# 2MB-Gary-Sel-v3.net
KiCad netlist of a schematic drawn in EAGLE
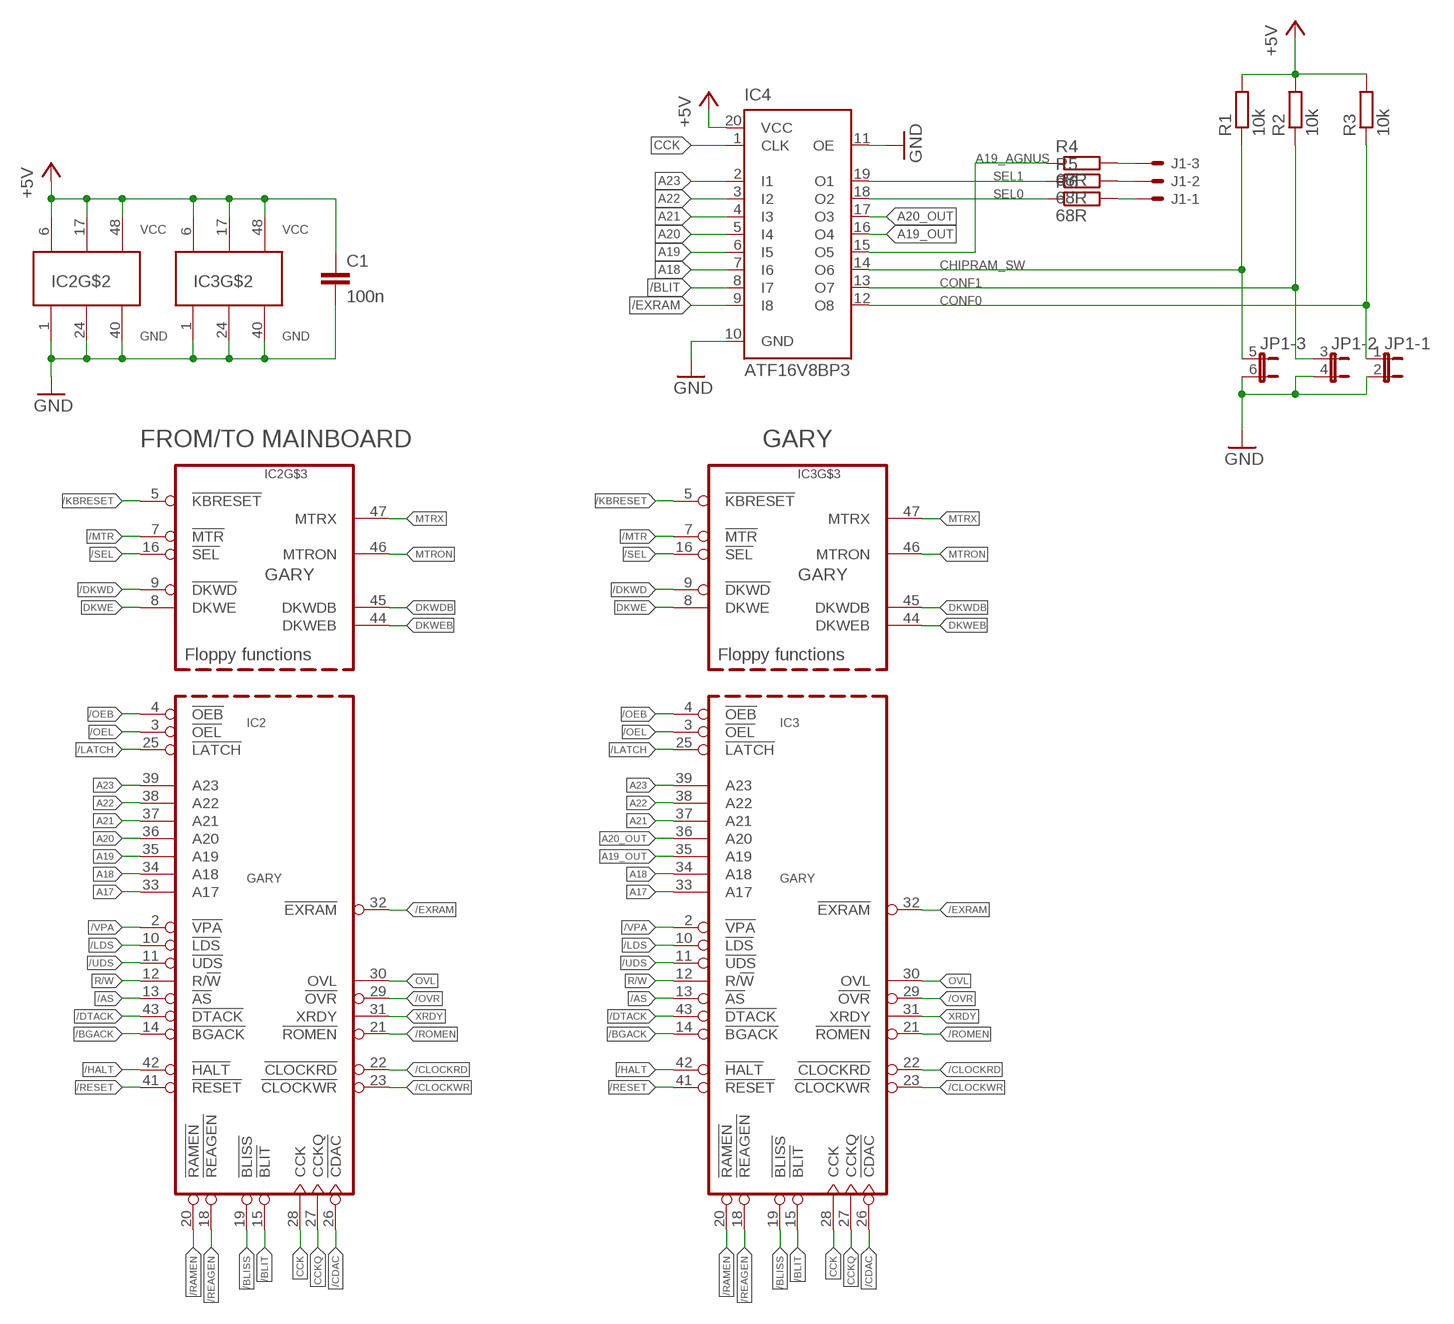
[diagram p0: schematic, sheet 1]

(export (version "E")
  (design (tool "Eeschema 10.0.6"))
  (components
    (comp (ref "C1")
      (value "100n")
      (footprint "eagle-import:C0805")
      (libsource (lib "eagle-import") (part "C-EUC0805"))
    )
    (comp (ref "IC2")
      (value "GARY_SOCKET")
      (footprint "eagle-import:DIP48-6NOPLACE")
      (libsource (lib "eagle-import") (part "GARYDIP48-6NOPLACE"))
    )
    (comp (ref "IC3")
      (value "GARY")
      (footprint "eagle-import:DIP48-6")
      (libsource (lib "eagle-import") (part "GARY_DIP"))
    )
    (comp (ref "IC4")
      (value "ATF16V8BP3")
      (footprint "eagle-import:DIL20")
      (fields (field (name "MPN") "ATF16V8CZ-15PU"))
      (libsource (lib "eagle-import") (part "ATF16V8BP3"))
    )
    (comp (ref "J1")
      (value "22-05-7038-03")
      (footprint "eagle-import:7395-03")
      (libsource (lib "eagle-import") (part "22-?-0305-7038"))
    )
    (comp (ref "JP1")
      (value "JP3QE")
      (footprint "eagle-import:JP3Q")
      (libsource (lib "eagle-import") (part "JP3QE"))
    )
    (comp (ref "R1")
      (value "10k")
      (footprint "eagle-import:R0805")
      (libsource (lib "eagle-import") (part "R-EU_R0805"))
    )
    (comp (ref "R2")
      (value "10k")
      (footprint "eagle-import:R0805")
      (libsource (lib "eagle-import") (part "R-EU_R0805"))
    )
    (comp (ref "R3")
      (value "10k")
      (footprint "eagle-import:R0805")
      (libsource (lib "eagle-import") (part "R-EU_R0805"))
    )
    (comp (ref "R4")
      (value "68R")
      (footprint "eagle-import:R0805")
      (libsource (lib "eagle-import") (part "R-EU_R0805"))
    )
    (comp (ref "R5")
      (value "68R")
      (footprint "eagle-import:R0805")
      (libsource (lib "eagle-import") (part "R-EU_R0805"))
    )
    (comp (ref "R6")
      (value "68R")
      (footprint "eagle-import:R0805")
      (libsource (lib "eagle-import") (part "R-EU_R0805"))
    )
  )
  (nets
    (net (code "1") (name "+5V") (class "Default")
      (node (ref "C1") (pin "1") (pinfunction "1_1") (pintype "passive"))
      (node (ref "IC2") (pin "17") (pinfunction "VCC_17") (pintype "power_in"))
      (node (ref "IC2") (pin "48") (pinfunction "VCC_48") (pintype "power_in"))
      (node (ref "IC2") (pin "6") (pinfunction "VCC_6") (pintype "power_in"))
      (node (ref "IC3") (pin "17") (pinfunction "VCC_17") (pintype "power_in"))
      (node (ref "IC3") (pin "48") (pinfunction "VCC_48") (pintype "power_in"))
      (node (ref "IC3") (pin "6") (pinfunction "VCC_6") (pintype "power_in"))
      (node (ref "IC4") (pin "20") (pinfunction "VCC_20") (pintype "power_in"))
      (node (ref "R1") (pin "2") (pinfunction "2_2") (pintype "passive"))
      (node (ref "R2") (pin "2") (pinfunction "2_2") (pintype "passive"))
      (node (ref "R3") (pin "2") (pinfunction "2_2") (pintype "passive"))
    )
    (net (code "2") (name "/A19_AGNUS") (class "Default")
      (node (ref "IC4") (pin "15") (pinfunction "O5_15") (pintype "output"))
      (node (ref "R4") (pin "1") (pinfunction "1_1") (pintype "passive"))
    )
    (net (code "3") (name "/CHIPRAM_SW") (class "Default")
      (node (ref "IC4") (pin "14") (pinfunction "O6_14") (pintype "output"))
      (node (ref "JP1") (pin "5") (pinfunction "1_5") (pintype "passive"))
      (node (ref "R1") (pin "1") (pinfunction "1_1") (pintype "passive"))
    )
    (net (code "4") (name "/CONF0") (class "Default")
      (node (ref "IC4") (pin "12") (pinfunction "O8_12") (pintype "output"))
      (node (ref "JP1") (pin "1") (pinfunction "1_1") (pintype "passive"))
      (node (ref "R3") (pin "1") (pinfunction "1_1") (pintype "passive"))
    )
    (net (code "5") (name "/CONF1") (class "Default")
      (node (ref "IC4") (pin "13") (pinfunction "O7_13") (pintype "output"))
      (node (ref "JP1") (pin "3") (pinfunction "1_3") (pintype "passive"))
      (node (ref "R2") (pin "1") (pinfunction "1_1") (pintype "passive"))
    )
    (net (code "6") (name "/SEL0") (class "Default")
      (node (ref "IC4") (pin "18") (pinfunction "O2_18") (pintype "output"))
      (node (ref "R6") (pin "1") (pinfunction "1_1") (pintype "passive"))
    )
    (net (code "7") (name "/SEL1") (class "Default")
      (node (ref "IC4") (pin "19") (pinfunction "O1_19") (pintype "output"))
      (node (ref "R5") (pin "1") (pinfunction "1_1") (pintype "passive"))
    )
    (net (code "8") (name "A17") (class "Default")
      (node (ref "IC2") (pin "33") (pinfunction "A17_33") (pintype "input"))
      (node (ref "IC3") (pin "33") (pinfunction "A17_33") (pintype "input"))
    )
    (net (code "9") (name "A18") (class "Default")
      (node (ref "IC2") (pin "34") (pinfunction "A18_34") (pintype "input"))
      (node (ref "IC3") (pin "34") (pinfunction "A18_34") (pintype "input"))
      (node (ref "IC4") (pin "7") (pinfunction "I6_7") (pintype "input"))
    )
    (net (code "10") (name "A19") (class "Default")
      (node (ref "IC2") (pin "35") (pinfunction "A19_35") (pintype "input"))
      (node (ref "IC4") (pin "6") (pinfunction "I5_6") (pintype "input"))
    )
    (net (code "11") (name "A19_OUT") (class "Default")
      (node (ref "IC3") (pin "35") (pinfunction "A19_35") (pintype "input"))
      (node (ref "IC4") (pin "16") (pinfunction "O4_16") (pintype "output"))
    )
    (net (code "12") (name "A20") (class "Default")
      (node (ref "IC2") (pin "36") (pinfunction "A20_36") (pintype "input"))
      (node (ref "IC4") (pin "5") (pinfunction "I4_5") (pintype "input"))
    )
    (net (code "13") (name "A20_OUT") (class "Default")
      (node (ref "IC3") (pin "36") (pinfunction "A20_36") (pintype "input"))
      (node (ref "IC4") (pin "17") (pinfunction "O3_17") (pintype "output"))
    )
    (net (code "14") (name "A21") (class "Default")
      (node (ref "IC2") (pin "37") (pinfunction "A21_37") (pintype "input"))
      (node (ref "IC3") (pin "37") (pinfunction "A21_37") (pintype "input"))
      (node (ref "IC4") (pin "4") (pinfunction "I3_4") (pintype "input"))
    )
    (net (code "15") (name "A22") (class "Default")
      (node (ref "IC2") (pin "38") (pinfunction "A22_38") (pintype "input"))
      (node (ref "IC3") (pin "38") (pinfunction "A22_38") (pintype "input"))
      (node (ref "IC4") (pin "3") (pinfunction "I2_3") (pintype "input"))
    )
    (net (code "16") (name "A23") (class "Default")
      (node (ref "IC2") (pin "39") (pinfunction "A23_39") (pintype "input"))
      (node (ref "IC3") (pin "39") (pinfunction "A23_39") (pintype "input"))
      (node (ref "IC4") (pin "2") (pinfunction "I1_2") (pintype "input"))
    )
    (net (code "17") (name "CCK") (class "Default")
      (node (ref "IC2") (pin "28") (pinfunction "CCK_28") (pintype "input"))
      (node (ref "IC3") (pin "28") (pinfunction "CCK_28") (pintype "input"))
      (node (ref "IC4") (pin "1") (pinfunction "CLK_1") (pintype "input"))
    )
    (net (code "18") (name "CCKQ") (class "Default")
      (node (ref "IC2") (pin "27") (pinfunction "CCKQ_27") (pintype "input"))
      (node (ref "IC3") (pin "27") (pinfunction "CCKQ_27") (pintype "input"))
    )
    (net (code "19") (name "DKWDB") (class "Default")
      (node (ref "IC2") (pin "45") (pinfunction "DKWDB_45") (pintype "output"))
      (node (ref "IC3") (pin "45") (pinfunction "DKWDB_45") (pintype "output"))
    )
    (net (code "20") (name "DKWE") (class "Default")
      (node (ref "IC2") (pin "8") (pinfunction "DKWE_8") (pintype "input"))
      (node (ref "IC3") (pin "8") (pinfunction "DKWE_8") (pintype "input"))
    )
    (net (code "21") (name "DKWEB") (class "Default")
      (node (ref "IC2") (pin "44") (pinfunction "DKWEB_44") (pintype "output"))
      (node (ref "IC3") (pin "44") (pinfunction "DKWEB_44") (pintype "output"))
    )
    (net (code "22") (name "GND") (class "Default")
      (node (ref "C1") (pin "2") (pinfunction "2_2") (pintype "passive"))
      (node (ref "IC2") (pin "1") (pinfunction "GND_1") (pintype "power_in"))
      (node (ref "IC2") (pin "24") (pinfunction "GND_24") (pintype "power_in"))
      (node (ref "IC2") (pin "40") (pinfunction "GND_40") (pintype "power_in"))
      (node (ref "IC3") (pin "1") (pinfunction "GND_1") (pintype "power_in"))
      (node (ref "IC3") (pin "24") (pinfunction "GND_24") (pintype "power_in"))
      (node (ref "IC3") (pin "40") (pinfunction "GND_40") (pintype "power_in"))
      (node (ref "IC4") (pin "10") (pinfunction "GND_10") (pintype "power_in"))
      (node (ref "IC4") (pin "11") (pinfunction "OE_11") (pintype "input"))
      (node (ref "JP1") (pin "2") (pinfunction "2_2") (pintype "passive"))
      (node (ref "JP1") (pin "4") (pinfunction "2_4") (pintype "passive"))
      (node (ref "JP1") (pin "6") (pinfunction "2_6") (pintype "passive"))
    )
    (net (code "23") (name "MTRON") (class "Default")
      (node (ref "IC2") (pin "46") (pinfunction "MTRON_46") (pintype "output"))
      (node (ref "IC3") (pin "46") (pinfunction "MTRON_46") (pintype "output"))
    )
    (net (code "24") (name "MTRX") (class "Default")
      (node (ref "IC2") (pin "47") (pinfunction "MTRX_47") (pintype "output"))
      (node (ref "IC3") (pin "47") (pinfunction "MTRX_47") (pintype "output"))
    )
    (net (code "25") (name "Net-(J1A-S)") (class "Default")
      (node (ref "J1") (pin "1") (pinfunction "S_1") (pintype "passive"))
      (node (ref "R6") (pin "2") (pinfunction "2_2") (pintype "passive"))
    )
    (net (code "26") (name "Net-(J1B-S)") (class "Default")
      (node (ref "J1") (pin "2") (pinfunction "S_2") (pintype "passive"))
      (node (ref "R5") (pin "2") (pinfunction "2_2") (pintype "passive"))
    )
    (net (code "27") (name "Net-(J1C-S)") (class "Default")
      (node (ref "J1") (pin "3") (pinfunction "S_3") (pintype "passive"))
      (node (ref "R4") (pin "2") (pinfunction "2_2") (pintype "passive"))
    )
    (net (code "28") (name "OVL") (class "Default")
      (node (ref "IC2") (pin "30") (pinfunction "OVL_30") (pintype "input"))
      (node (ref "IC3") (pin "30") (pinfunction "OVL_30") (pintype "input"))
    )
    (net (code "29") (name "R{slash}W") (class "Default")
      (node (ref "IC2") (pin "12") (pinfunction "R/~{W}_12") (pintype "input"))
      (node (ref "IC3") (pin "12") (pinfunction "R/~{W}_12") (pintype "input"))
    )
    (net (code "30") (name "XRDY") (class "Default")
      (node (ref "IC2") (pin "31") (pinfunction "XRDY_31") (pintype "input"))
      (node (ref "IC3") (pin "31") (pinfunction "XRDY_31") (pintype "input"))
    )
    (net (code "31") (name "{slash}AS") (class "Default")
      (node (ref "IC2") (pin "13") (pinfunction "~{AS}_13") (pintype "input"))
      (node (ref "IC3") (pin "13") (pinfunction "~{AS}_13") (pintype "input"))
    )
    (net (code "32") (name "{slash}BGACK") (class "Default")
      (node (ref "IC2") (pin "14") (pinfunction "~{BGACK}_14") (pintype "input"))
      (node (ref "IC3") (pin "14") (pinfunction "~{BGACK}_14") (pintype "input"))
    )
    (net (code "33") (name "{slash}BLISS") (class "Default")
      (node (ref "IC2") (pin "19") (pinfunction "~{BLISS}_19") (pintype "output"))
      (node (ref "IC3") (pin "19") (pinfunction "~{BLISS}_19") (pintype "output"))
    )
    (net (code "34") (name "{slash}BLIT") (class "Default")
      (node (ref "IC2") (pin "15") (pinfunction "~{BLIT}_15") (pintype "input"))
      (node (ref "IC3") (pin "15") (pinfunction "~{BLIT}_15") (pintype "input"))
      (node (ref "IC4") (pin "8") (pinfunction "I7_8") (pintype "input"))
    )
    (net (code "35") (name "{slash}CDAC") (class "Default")
      (node (ref "IC2") (pin "26") (pinfunction "~{CDAC}_26") (pintype "input"))
      (node (ref "IC3") (pin "26") (pinfunction "~{CDAC}_26") (pintype "input"))
    )
    (net (code "36") (name "{slash}CLOCKRD") (class "Default")
      (node (ref "IC2") (pin "22") (pinfunction "~{CLOCKRD}_22") (pintype "output"))
      (node (ref "IC3") (pin "22") (pinfunction "~{CLOCKRD}_22") (pintype "output"))
    )
    (net (code "37") (name "{slash}CLOCKWR") (class "Default")
      (node (ref "IC2") (pin "23") (pinfunction "~{CLOCKWR}_23") (pintype "output"))
      (node (ref "IC3") (pin "23") (pinfunction "~{CLOCKWR}_23") (pintype "output"))
    )
    (net (code "38") (name "{slash}DKWD") (class "Default")
      (node (ref "IC2") (pin "9") (pinfunction "~{DKWD}_9") (pintype "input"))
      (node (ref "IC3") (pin "9") (pinfunction "~{DKWD}_9") (pintype "input"))
    )
    (net (code "39") (name "{slash}DTACK") (class "Default")
      (node (ref "IC2") (pin "43") (pinfunction "~{DTACK}_43") (pintype "output"))
      (node (ref "IC3") (pin "43") (pinfunction "~{DTACK}_43") (pintype "output"))
    )
    (net (code "40") (name "{slash}EXRAM") (class "Default")
      (node (ref "IC2") (pin "32") (pinfunction "~{EXRAM}_32") (pintype "input"))
      (node (ref "IC3") (pin "32") (pinfunction "~{EXRAM}_32") (pintype "input"))
      (node (ref "IC4") (pin "9") (pinfunction "I8_9") (pintype "input"))
    )
    (net (code "41") (name "{slash}HALT") (class "Default")
      (node (ref "IC2") (pin "42") (pinfunction "~{HALT}_42") (pintype "output"))
      (node (ref "IC3") (pin "42") (pinfunction "~{HALT}_42") (pintype "output"))
    )
    (net (code "42") (name "{slash}KBRESET") (class "Default")
      (node (ref "IC2") (pin "5") (pinfunction "~{KBRESET}_5") (pintype "input"))
      (node (ref "IC3") (pin "5") (pinfunction "~{KBRESET}_5") (pintype "input"))
    )
    (net (code "43") (name "{slash}LATCH") (class "Default")
      (node (ref "IC2") (pin "25") (pinfunction "~{LATCH}_25") (pintype "output"))
      (node (ref "IC3") (pin "25") (pinfunction "~{LATCH}_25") (pintype "output"))
    )
    (net (code "44") (name "{slash}LDS") (class "Default")
      (node (ref "IC2") (pin "10") (pinfunction "~{LDS}_10") (pintype "input"))
      (node (ref "IC3") (pin "10") (pinfunction "~{LDS}_10") (pintype "input"))
    )
    (net (code "45") (name "{slash}MTR") (class "Default")
      (node (ref "IC2") (pin "7") (pinfunction "~{MTR}_7") (pintype "input"))
      (node (ref "IC3") (pin "7") (pinfunction "~{MTR}_7") (pintype "input"))
    )
    (net (code "46") (name "{slash}OEB") (class "Default")
      (node (ref "IC2") (pin "4") (pinfunction "~{OEB}_4") (pintype "output"))
      (node (ref "IC3") (pin "4") (pinfunction "~{OEB}_4") (pintype "output"))
    )
    (net (code "47") (name "{slash}OEL") (class "Default")
      (node (ref "IC2") (pin "3") (pinfunction "~{OEL}_3") (pintype "output"))
      (node (ref "IC3") (pin "3") (pinfunction "~{OEL}_3") (pintype "output"))
    )
    (net (code "48") (name "{slash}OVR") (class "Default")
      (node (ref "IC2") (pin "29") (pinfunction "~{OVR}_29") (pintype "input"))
      (node (ref "IC3") (pin "29") (pinfunction "~{OVR}_29") (pintype "input"))
    )
    (net (code "49") (name "{slash}RAMEN") (class "Default")
      (node (ref "IC2") (pin "20") (pinfunction "~{RAMEN}_20") (pintype "output"))
      (node (ref "IC3") (pin "20") (pinfunction "~{RAMEN}_20") (pintype "output"))
    )
    (net (code "50") (name "{slash}REAGEN") (class "Default")
      (node (ref "IC2") (pin "18") (pinfunction "~{REAGEN}_18") (pintype "output"))
      (node (ref "IC3") (pin "18") (pinfunction "~{REAGEN}_18") (pintype "output"))
    )
    (net (code "51") (name "{slash}RESET") (class "Default")
      (node (ref "IC2") (pin "41") (pinfunction "~{RESET}_41") (pintype "output"))
      (node (ref "IC3") (pin "41") (pinfunction "~{RESET}_41") (pintype "output"))
    )
    (net (code "52") (name "{slash}ROMEN") (class "Default")
      (node (ref "IC2") (pin "21") (pinfunction "~{ROMEN}_21") (pintype "output"))
      (node (ref "IC3") (pin "21") (pinfunction "~{ROMEN}_21") (pintype "output"))
    )
    (net (code "53") (name "{slash}SEL") (class "Default")
      (node (ref "IC2") (pin "16") (pinfunction "~{SEL}_16") (pintype "input"))
      (node (ref "IC3") (pin "16") (pinfunction "~{SEL}_16") (pintype "input"))
    )
    (net (code "54") (name "{slash}UDS") (class "Default")
      (node (ref "IC2") (pin "11") (pinfunction "~{UDS}_11") (pintype "input"))
      (node (ref "IC3") (pin "11") (pinfunction "~{UDS}_11") (pintype "input"))
    )
    (net (code "55") (name "{slash}VPA") (class "Default")
      (node (ref "IC2") (pin "2") (pinfunction "~{VPA}_2") (pintype "output"))
      (node (ref "IC3") (pin "2") (pinfunction "~{VPA}_2") (pintype "output"))
    )
  )
)
